# Supply_Magneto.net
KiCad netlist of a schematic drawn in Altium Designer
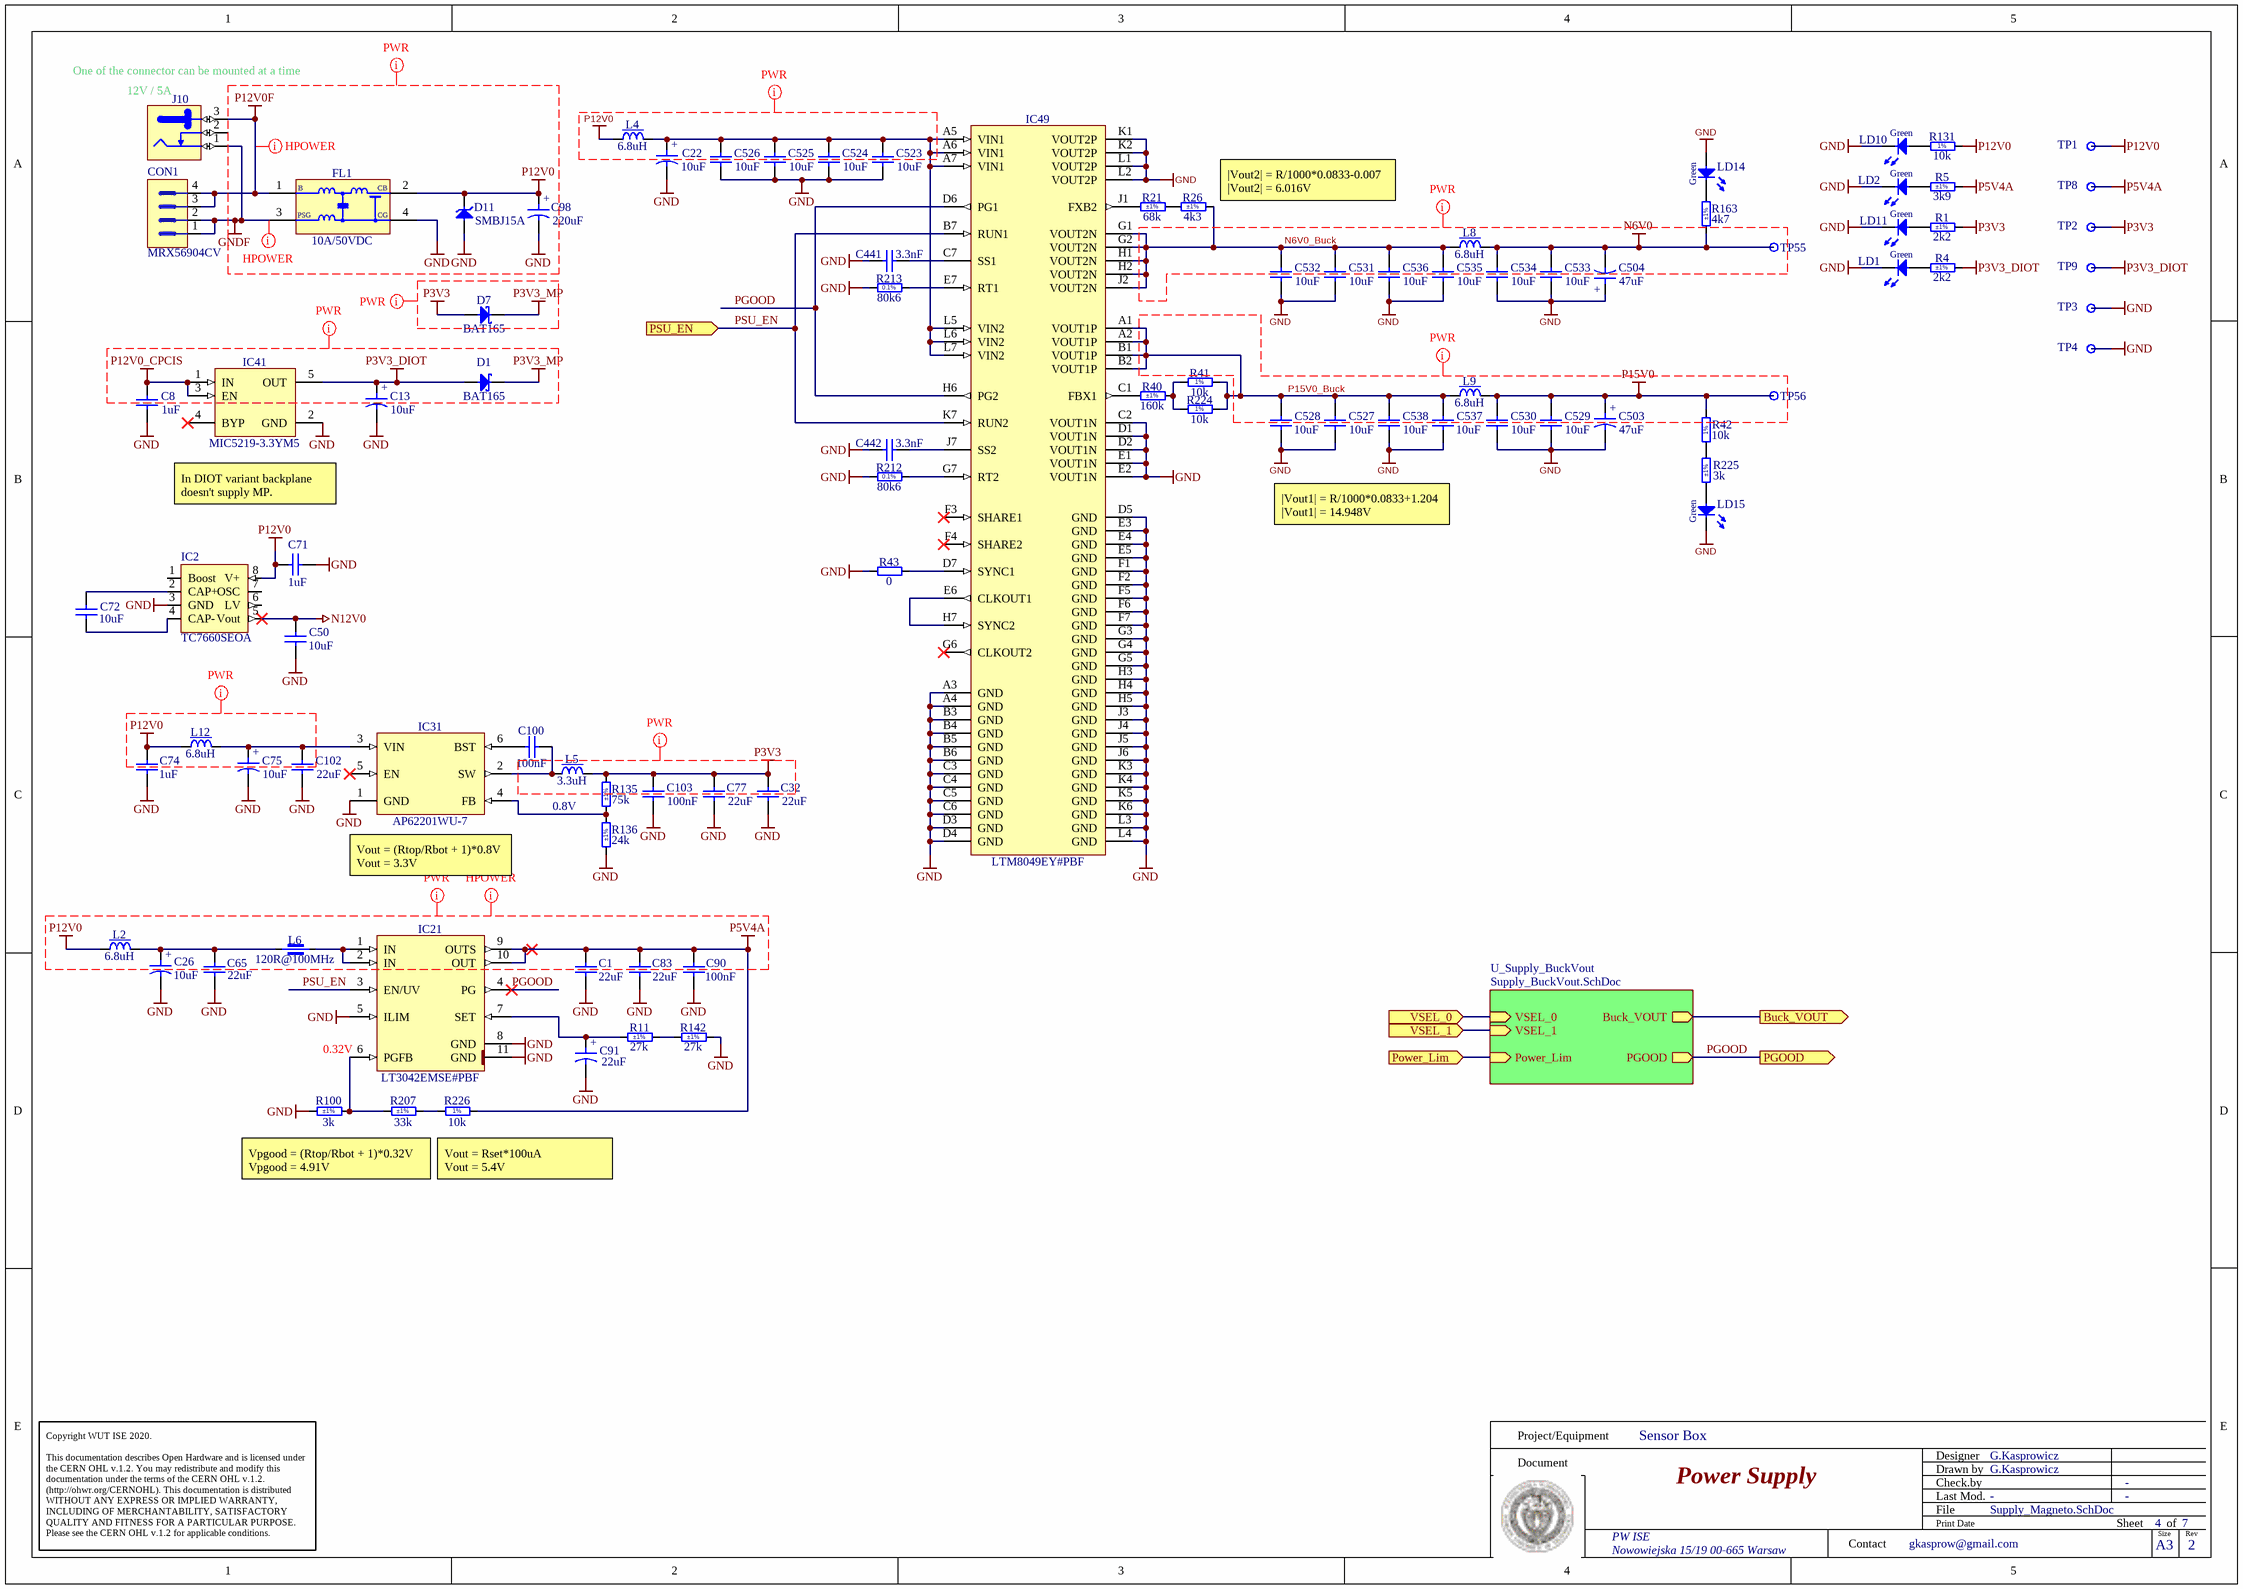
[diagram p0: Supply_Magneto.SchDoc]

(export (version "E")
  (design (tool "Eeschema 10.0.6"))
  (components
    (comp (ref "C1")
      (value "22uF")
      (footprint "CAPC2012X135N")
      (description "Non-polarised capacitor")
      (fields (field (name "PART NUMBER") "CC0805_22UF_16V_10%_X5R") (field (name "VOLTAGE") "16V"))
      (libsource (lib "Capacitors") (part "Capacitor - non polarized"))
    )
    (comp (ref "C8")
      (value "1uF")
      (footprint "CAPC1608X87N")
      (description "Non-polarised capacitor")
      (fields (field (name "PART NUMBER") "CC0603_1UF_25V_10%_X7R") (field (name "VOLTAGE") "25V"))
      (libsource (lib "Capacitors") (part "Capacitor - non polarized"))
    )
    (comp (ref "C13")
      (value "10uF")
      (footprint "CAPMP3216X180N")
      (description "Polarised capacitor")
      (fields (field (name "PART NUMBER") "CTE3216-18_10UF_16V_20%_AVX_TCJ") (field (name "VOLTAGE") "16V"))
      (libsource (lib "Capacitors") (part "Capacitor - polarized"))
    )
    (comp (ref "C22")
      (value "10uF")
      (footprint "CAPMP3216X180N")
      (description "Polarised capacitor")
      (fields (field (name "PART NUMBER") "CTE3216-18_10UF_16V_20%_AVX_TCJ") (field (name "VOLTAGE") "16V"))
      (libsource (lib "Capacitors") (part "Capacitor - polarized"))
    )
    (comp (ref "C26")
      (value "10uF")
      (footprint "CAPMP3216X180N")
      (description "Polarised capacitor")
      (fields (field (name "PART NUMBER") "CTE3216-18_10UF_16V_20%_AVX_TCJ") (field (name "VOLTAGE") "16V"))
      (libsource (lib "Capacitors") (part "Capacitor - polarized"))
    )
    (comp (ref "C32")
      (value "22uF")
      (footprint "CAPC2012X135N")
      (description "Non-polarised capacitor")
      (fields (field (name "PART NUMBER") "CC0805_22UF_16V_10%_X5R") (field (name "VOLTAGE") "16V"))
      (libsource (lib "Capacitors") (part "Capacitor - non polarized"))
    )
    (comp (ref "C50")
      (value "10uF")
      (footprint "CAPC1608X80N")
      (description "Non-polarised capacitor")
      (fields (field (name "PART NUMBER") "CC0603_10UF_16V_20%_X5R") (field (name "VOLTAGE") "16V"))
      (libsource (lib "Capacitors") (part "Capacitor - non polarized"))
    )
    (comp (ref "C65")
      (value "22uF")
      (footprint "CAPC2012X135N")
      (description "Non-polarised capacitor")
      (fields (field (name "PART NUMBER") "CC0805_22UF_16V_10%_X5R") (field (name "VOLTAGE") "16V"))
      (libsource (lib "Capacitors") (part "Capacitor - non polarized"))
    )
    (comp (ref "C71")
      (value "1uF")
      (footprint "CAPC1608X87N")
      (description "Non-polarised capacitor")
      (fields (field (name "PART NUMBER") "CC0603_1UF_25V_10%_X7R") (field (name "VOLTAGE") "25V"))
      (libsource (lib "Capacitors") (part "Capacitor - non polarized"))
    )
    (comp (ref "C72")
      (value "10uF")
      (footprint "CAPC1608X80N")
      (description "Non-polarised capacitor")
      (fields (field (name "PART NUMBER") "CC0603_10UF_16V_20%_X5R") (field (name "VOLTAGE") "16V"))
      (libsource (lib "Capacitors") (part "Capacitor - non polarized"))
    )
    (comp (ref "C74")
      (value "1uF")
      (footprint "CAPC1608X87N")
      (description "Non-polarised capacitor")
      (fields (field (name "PART NUMBER") "CC0603_1UF_25V_10%_X7R") (field (name "VOLTAGE") "25V"))
      (libsource (lib "Capacitors") (part "Capacitor - non polarized"))
    )
    (comp (ref "C75")
      (value "10uF")
      (footprint "CAPMP3216X180N")
      (description "Polarised capacitor")
      (fields (field (name "PART NUMBER") "CTE3216-18_10UF_16V_20%_AVX_TCJ") (field (name "VOLTAGE") "16V"))
      (libsource (lib "Capacitors") (part "Capacitor - polarized"))
    )
    (comp (ref "C77")
      (value "22uF")
      (footprint "CAPC2012X135N")
      (description "Non-polarised capacitor")
      (fields (field (name "PART NUMBER") "CC0805_22UF_16V_10%_X5R") (field (name "VOLTAGE") "16V"))
      (libsource (lib "Capacitors") (part "Capacitor - non polarized"))
    )
    (comp (ref "C83")
      (value "22uF")
      (footprint "CAPC2012X135N")
      (description "Non-polarised capacitor")
      (fields (field (name "PART NUMBER") "CC0805_22UF_16V_10%_X5R") (field (name "VOLTAGE") "16V"))
      (libsource (lib "Capacitors") (part "Capacitor - non polarized"))
    )
    (comp (ref "C90")
      (value "100nF")
      (footprint "CAPC1005X55N")
      (description "Non-polarised capacitor")
      (fields (field (name "PART NUMBER") "CC0402_100NF_16V_10%_X5R") (field (name "VOLTAGE") "16V"))
      (libsource (lib "Capacitors") (part "Capacitor - non polarized"))
    )
    (comp (ref "C91")
      (value "22uF")
      (footprint "CAPMP3528X210N")
      (description "Polarised capacitor")
      (fields (field (name "PART NUMBER") "CTE3528-21_22UF_10V_10%_LESR0700") (field (name "VOLTAGE") "10V"))
      (libsource (lib "Capacitors") (part "Capacitor - polarized"))
    )
    (comp (ref "C98")
      (value "220uF")
      (footprint "CAPAE830X620N")
      (description "Polarised capacitor")
      (fields (field (name "PART NUMBER") "CAE830-620_220UF_16V_20%") (field (name "VOLTAGE") "16V"))
      (libsource (lib "Capacitors") (part "Capacitor - polarized"))
    )
    (comp (ref "C100")
      (value "100nF")
      (footprint "CAPC1005X55N")
      (description "Non-polarised capacitor")
      (fields (field (name "PART NUMBER") "CC0402_100NF_16V_10%_X5R") (field (name "VOLTAGE") "16V"))
      (libsource (lib "Capacitors") (part "Capacitor - non polarized"))
    )
    (comp (ref "C102")
      (value "22uF")
      (footprint "CAPC2012X135N")
      (description "Non-polarised capacitor")
      (fields (field (name "PART NUMBER") "CC0805_22UF_16V_10%_X5R") (field (name "VOLTAGE") "16V"))
      (libsource (lib "Capacitors") (part "Capacitor - non polarized"))
    )
    (comp (ref "C103")
      (value "100nF")
      (footprint "CAPC1005X55N")
      (description "Non-polarised capacitor")
      (fields (field (name "PART NUMBER") "CC0402_100NF_16V_10%_X5R") (field (name "VOLTAGE") "16V"))
      (libsource (lib "Capacitors") (part "Capacitor - non polarized"))
    )
    (comp (ref "C441")
      (value "3.3nF")
      (footprint "CAPC1005X55N")
      (description "Non-polarised capacitor")
      (fields
        (field (name "MANUFACTURER PART NUMBER") "CC0402_3.3NF_50V_10%_X7R")
        (field (name "MANUFACTURER") "GENERIC")
      )
      (libsource (lib "Capacitors") (part "Capacitor - non polarized"))
    )
    (comp (ref "C442")
      (value "3.3nF")
      (footprint "CAPC1005X55N")
      (description "Non-polarised capacitor")
      (fields
        (field (name "MANUFACTURER PART NUMBER") "CC0402_3.3NF_50V_10%_X7R")
        (field (name "MANUFACTURER") "GENERIC")
      )
      (libsource (lib "Capacitors") (part "Capacitor - non polarized"))
    )
    (comp (ref "C503")
      (value "47uF")
      (footprint "CAPMP6032X280N")
      (description "Polarised capacitor")
      (fields
        (field (name "MANUFACTURER PART NUMBER") "CTE6032-28_47UF_16V_10%_LESR0350")
        (field (name "MANUFACTURER") "GENERIC")
      )
      (libsource (lib "Capacitors") (part "Capacitor - polarized"))
    )
    (comp (ref "C504")
      (value "47uF")
      (footprint "CAPMP6032X280N")
      (description "Polarised capacitor")
      (fields
        (field (name "MANUFACTURER PART NUMBER") "CTE6032-28_47UF_16V_10%_LESR0350")
        (field (name "MANUFACTURER") "GENERIC")
      )
      (libsource (lib "Capacitors") (part "Capacitor - polarized"))
    )
    (comp (ref "C523")
      (value "10uF")
      (footprint "CAPC2012X95N")
      (description "Non-polarised capacitor")
      (fields
        (field (name "MANUFACTURER PART NUMBER") "CC0805_10UF_25V_10%_X5R")
        (field (name "MANUFACTURER") "GENERIC")
      )
      (libsource (lib "Capacitors") (part "Capacitor - non polarized"))
    )
    (comp (ref "C524")
      (value "10uF")
      (footprint "CAPC2012X95N")
      (description "Non-polarised capacitor")
      (fields
        (field (name "MANUFACTURER PART NUMBER") "CC0805_10UF_25V_10%_X5R")
        (field (name "MANUFACTURER") "GENERIC")
      )
      (libsource (lib "Capacitors") (part "Capacitor - non polarized"))
    )
    (comp (ref "C525")
      (value "10uF")
      (footprint "CAPC2012X95N")
      (description "Non-polarised capacitor")
      (fields
        (field (name "MANUFACTURER PART NUMBER") "CC0805_10UF_25V_10%_X5R")
        (field (name "MANUFACTURER") "GENERIC")
      )
      (libsource (lib "Capacitors") (part "Capacitor - non polarized"))
    )
    (comp (ref "C526")
      (value "10uF")
      (footprint "CAPC2012X95N")
      (description "Non-polarised capacitor")
      (fields
        (field (name "MANUFACTURER PART NUMBER") "CC0805_10UF_25V_10%_X5R")
        (field (name "MANUFACTURER") "GENERIC")
      )
      (libsource (lib "Capacitors") (part "Capacitor - non polarized"))
    )
    (comp (ref "C527")
      (value "10uF")
      (footprint "CAPC2012X95N")
      (description "Non-polarised capacitor")
      (fields
        (field (name "MANUFACTURER PART NUMBER") "CC0805_10UF_25V_10%_X5R")
        (field (name "MANUFACTURER") "GENERIC")
      )
      (libsource (lib "Capacitors") (part "Capacitor - non polarized"))
    )
    (comp (ref "C528")
      (value "10uF")
      (footprint "CAPC2012X95N")
      (description "Non-polarised capacitor")
      (fields
        (field (name "MANUFACTURER PART NUMBER") "CC0805_10UF_25V_10%_X5R")
        (field (name "MANUFACTURER") "GENERIC")
      )
      (libsource (lib "Capacitors") (part "Capacitor - non polarized"))
    )
    (comp (ref "C529")
      (value "10uF")
      (footprint "CAPC2012X95N")
      (description "Non-polarised capacitor")
      (fields
        (field (name "MANUFACTURER PART NUMBER") "CC0805_10UF_25V_10%_X5R")
        (field (name "MANUFACTURER") "GENERIC")
      )
      (libsource (lib "Capacitors") (part "Capacitor - non polarized"))
    )
    (comp (ref "C530")
      (value "10uF")
      (footprint "CAPC2012X95N")
      (description "Non-polarised capacitor")
      (fields
        (field (name "MANUFACTURER PART NUMBER") "CC0805_10UF_25V_10%_X5R")
        (field (name "MANUFACTURER") "GENERIC")
      )
      (libsource (lib "Capacitors") (part "Capacitor - non polarized"))
    )
    (comp (ref "C531")
      (value "10uF")
      (footprint "CAPC2012X95N")
      (description "Non-polarised capacitor")
      (fields
        (field (name "MANUFACTURER PART NUMBER") "CC0805_10UF_25V_10%_X5R")
        (field (name "MANUFACTURER") "GENERIC")
      )
      (libsource (lib "Capacitors") (part "Capacitor - non polarized"))
    )
    (comp (ref "C532")
      (value "10uF")
      (footprint "CAPC2012X95N")
      (description "Non-polarised capacitor")
      (fields
        (field (name "MANUFACTURER PART NUMBER") "CC0805_10UF_25V_10%_X5R")
        (field (name "MANUFACTURER") "GENERIC")
      )
      (libsource (lib "Capacitors") (part "Capacitor - non polarized"))
    )
    (comp (ref "C533")
      (value "10uF")
      (footprint "CAPC2012X95N")
      (description "Non-polarised capacitor")
      (fields
        (field (name "MANUFACTURER PART NUMBER") "CC0805_10UF_25V_10%_X5R")
        (field (name "MANUFACTURER") "GENERIC")
      )
      (libsource (lib "Capacitors") (part "Capacitor - non polarized"))
    )
    (comp (ref "C534")
      (value "10uF")
      (footprint "CAPC2012X95N")
      (description "Non-polarised capacitor")
      (fields
        (field (name "MANUFACTURER PART NUMBER") "CC0805_10UF_25V_10%_X5R")
        (field (name "MANUFACTURER") "GENERIC")
      )
      (libsource (lib "Capacitors") (part "Capacitor - non polarized"))
    )
    (comp (ref "C535")
      (value "10uF")
      (footprint "CAPC2012X95N")
      (description "Non-polarised capacitor")
      (fields
        (field (name "MANUFACTURER PART NUMBER") "CC0805_10UF_25V_10%_X5R")
        (field (name "MANUFACTURER") "GENERIC")
      )
      (libsource (lib "Capacitors") (part "Capacitor - non polarized"))
    )
    (comp (ref "C536")
      (value "10uF")
      (footprint "CAPC2012X95N")
      (description "Non-polarised capacitor")
      (fields
        (field (name "MANUFACTURER PART NUMBER") "CC0805_10UF_25V_10%_X5R")
        (field (name "MANUFACTURER") "GENERIC")
      )
      (libsource (lib "Capacitors") (part "Capacitor - non polarized"))
    )
    (comp (ref "C537")
      (value "10uF")
      (footprint "CAPC2012X95N")
      (description "Non-polarised capacitor")
      (fields
        (field (name "MANUFACTURER PART NUMBER") "CC0805_10UF_25V_10%_X5R")
        (field (name "MANUFACTURER") "GENERIC")
      )
      (libsource (lib "Capacitors") (part "Capacitor - non polarized"))
    )
    (comp (ref "C538")
      (value "10uF")
      (footprint "CAPC2012X95N")
      (description "Non-polarised capacitor")
      (fields
        (field (name "MANUFACTURER PART NUMBER") "CC0805_10UF_25V_10%_X5R")
        (field (name "MANUFACTURER") "GENERIC")
      )
      (libsource (lib "Capacitors") (part "Capacitor - non polarized"))
    )
    (comp (ref "CON1")
      (value "MRX56904CV")
      (footprint "MRX56904CV")
      (description "4.2mm cripm terminal header")
      (fields (field (name "MANUFACTURER1 PART NUMBER") "64900429522"))
      (libsource (lib "LIBRARY_SCH") (part "CON_CRIMP_4.2mm_RA_4"))
    )
    (comp (ref "D1")
      (value "BAT165")
      (footprint "SOD2512X110N")
      (description "Schottky Diode")
      (fields (field (name "MANUFACTURER") "INFINEON") (field (name "VOLTAGE") "40V"))
      (libsource (lib "ICs And Semiconductors") (part "Diode Schottky"))
    )
    (comp (ref "D7")
      (value "BAT165")
      (footprint "SOD2512X110N")
      (description "Schottky Diode")
      (fields (field (name "VOLTAGE") "40V") (field (name "POWER") "750mA"))
      (libsource (lib "ICs And Semiconductors") (part "Diode Schottky"))
    )
    (comp (ref "D11")
      (value "SMBJ15A")
      (footprint "DIOM5336X265N")
      (description "Zener Diode")
      (fields (field (name "VOLTAGE") "15V") (field (name "POWER") "600W"))
      (libsource (lib "ICs And Semiconductors") (part "Diode Zener"))
    )
    (comp (ref "FL1")
      (value "10A/50VDC")
      (footprint "FIL_MURATA_BNX02")
      (description "Block Type EMIFIL (LC Combined)")
      (fields
        (field (name "PART NUMBER") "FIL_MURATA_BNX022-01L")
        (field (name "MANUFACTURER1 PART NUMBER") "BNX022-01L")
      )
      (libsource (lib "Inductors & Transformers") (part "FIL_MURATA_BNX02"))
    )
    (comp (ref "IC2")
      (value "TC7660SEOA")
      (footprint "SO-8")
      (description "20mA PUMP DC-TO-DC VOLTAGE CONVERTER")
      (libsource (lib "LIBRARY_SCH") (part "PM_TC7660"))
    )
    (comp (ref "IC21")
      (value "LT3042EMSE#PBF")
      (footprint "SOP50P490X110-11N-R168X198")
      (description "20V, 200mA, Ultralow Noise, Ultrahigh PSRR RF Linear Regulator")
      (libsource (lib "ICs And Semiconductors") (part "LT3042"))
    )
    (comp (ref "IC31")
      (value "AP62201WU-7")
      (footprint "SOT95P280X100-6N")
      (description "4.2V TO 18V INPUT, 2A LOW IQ SYNCHRONOUS BUCK CONVERTER")
      (libsource (lib "ICs And Semiconductors") (part "AP62201WU"))
    )
    (comp (ref "IC41")
      (value "MIC5219-3.3YM5")
      (footprint "SOT95P280X145-5N")
      (description "500mA Peak Output LDO Regulator")
      (fields (field (name "MANUFACTURER1 PART NUMBER") "MIC5219-3.3YM5-TR"))
      (libsource (lib "ICs And Semiconductors") (part "MIC5219-X.XYM5"))
    )
    (comp (ref "IC49")
      (value "LTM8049EY#PBF")
      (footprint "BGA77C127P7X11_900X1500X262")
      (description "Dual SEPIC or Inverting uModule DC/DC Converter")
      (libsource (lib "ICs And Semiconductors") (part "LTM8049"))
    )
    (comp (ref "J10")
      (value "Jack")
      (footprint "SWITCHCRAFT_L712RA")
      (description "24V /3. 5A, 2.1mm Diameter Pin, SMD DC Power Supply Connector With  Break Contact")
      (fields (field (name "PART NUMBER") "SWITCHCRAFT_L712RA") (field (name "MANUFACTURER") "SWITCHCRAFT"))
      (libsource (lib "LIBRARY_SCH") (part "CON_DC_5A_THT_RA"))
    )
    (comp (ref "L2")
      (value "6.8uH")
      (footprint "IND_COILCRAFT_XAL4030")
      (description "Inductor With Core")
      (fields (field (name "PART NUMBER") "IND_6.8UH_20%_COILCRAFT_XAL4030") (field (name "POWER") "3A"))
      (libsource (lib "Inductors & Transformers") (part "Inductor With Magnetic core"))
    )
    (comp (ref "L4")
      (value "6.8uH")
      (footprint "IND_COILCRAFT_XAL4030")
      (description "Inductor With Core")
      (fields (field (name "PART NUMBER") "IND_6.8UH_20%_COILCRAFT_XAL4030") (field (name "POWER") "3A"))
      (libsource (lib "Inductors & Transformers") (part "Inductor With Magnetic core"))
    )
    (comp (ref "L5")
      (value "3.3uH")
      (footprint "IND_WURTH_WE-TPC_4828")
      (description "Inductor With Core")
      (fields
        (field (name "PART NUMBER") "IND_3.3UH_30%_WURTH_WE-TPC_744043003")
        (field (name "POWER") "2.15A")
      )
      (libsource (lib "Inductors & Transformers") (part "Inductor With Magnetic core"))
    )
    (comp (ref "L6")
      (value "120R@100MHz")
      (footprint "INDC1608X65N")
      (fields
        (field (name "PART NUMBER") "IND0603_MURATA_BLM18SG121TN1D")
        (field (name "POWER") "3A")
        (field (name "TOLERANCE") "±25%")
      )
      (libsource (lib "Inductors & Transformers") (part "Ferrite Bead"))
    )
    (comp (ref "L8")
      (value "6.8uH")
      (footprint "IND_COILCRAFT_XAL4030")
      (description "Inductor With Core")
      (fields (field (name "PART NUMBER") "IND_6.8UH_20%_COILCRAFT_XAL4030") (field (name "POWER") "3A"))
      (libsource (lib "Inductors & Transformers") (part "Inductor With Magnetic core"))
    )
    (comp (ref "L9")
      (value "6.8uH")
      (footprint "IND_COILCRAFT_XAL4030")
      (description "Inductor With Core")
      (fields (field (name "PART NUMBER") "IND_6.8UH_20%_COILCRAFT_XAL4030") (field (name "POWER") "3A"))
      (libsource (lib "Inductors & Transformers") (part "Inductor With Magnetic core"))
    )
    (comp (ref "L12")
      (value "6.8uH")
      (footprint "IND_COILCRAFT_XAL4030")
      (description "Inductor With Core")
      (fields (field (name "PART NUMBER") "IND_6.8UH_20%_COILCRAFT_XAL4030") (field (name "POWER") "3A"))
      (libsource (lib "Inductors & Transformers") (part "Inductor With Magnetic core"))
    )
    (comp (ref "LD1")
      (value "Green")
      (footprint "LED_KINGBRIGHT_KPH-1608CGCK")
      (description "LED Green 1C 2A")
      (fields
        (field (name "PART NUMBER") "LED_KINGBRIGHT_KPH-1608CGCK")
        (field (name "MANUFACTURER1 PART NUMBER") "KPH-1608CGCK")
      )
      (libsource (lib "ICs And Semiconductors") (part "LED Green 1C 2A"))
    )
    (comp (ref "LD2")
      (value "Green")
      (footprint "LED_KINGBRIGHT_KPH-1608CGCK")
      (description "LED Green 1C 2A")
      (fields
        (field (name "PART NUMBER") "LED_KINGBRIGHT_KPH-1608CGCK")
        (field (name "MANUFACTURER1 PART NUMBER") "KPH-1608CGCK")
      )
      (libsource (lib "ICs And Semiconductors") (part "LED Green 1C 2A"))
    )
    (comp (ref "LD10")
      (value "Green")
      (footprint "LED_KINGBRIGHT_KPH-1608CGCK")
      (description "LED Green 1C 2A")
      (fields
        (field (name "PART NUMBER") "LED_KINGBRIGHT_KPH-1608CGCK")
        (field (name "MANUFACTURER1 PART NUMBER") "KPH-1608CGCK")
      )
      (libsource (lib "ICs And Semiconductors") (part "LED Green 1C 2A"))
    )
    (comp (ref "LD11")
      (value "Green")
      (footprint "LED_KINGBRIGHT_KPH-1608CGCK")
      (description "LED Green 1C 2A")
      (fields
        (field (name "PART NUMBER") "LED_KINGBRIGHT_KPH-1608CGCK")
        (field (name "MANUFACTURER1 PART NUMBER") "KPH-1608CGCK")
      )
      (libsource (lib "ICs And Semiconductors") (part "LED Green 1C 2A"))
    )
    (comp (ref "LD14")
      (value "Green")
      (footprint "LED_KINGBRIGHT_KPH-1608CGCK")
      (description "LED Green 1C 2A")
      (fields
        (field (name "MANUFACTURER1 PART NUMBER") "KPH-1608CGCK")
        (field (name "PART NUMBER") "LED_KINGBRIGHT_KPH-1608CGCK")
      )
      (libsource (lib "ICs And Semiconductors") (part "LED Green 1C 2A"))
    )
    (comp (ref "LD15")
      (value "Green")
      (footprint "LED_KINGBRIGHT_KPH-1608CGCK")
      (description "LED Green 1C 2A")
      (fields
        (field (name "MANUFACTURER1 PART NUMBER") "KPH-1608CGCK")
        (field (name "PART NUMBER") "LED_KINGBRIGHT_KPH-1608CGCK")
      )
      (libsource (lib "ICs And Semiconductors") (part "LED Green 1C 2A"))
    )
    (comp (ref "R1")
      (value "2k2")
      (footprint "RESC1608X55N")
      (description "Resistor - 1%")
      (fields
        (field (name "TOLERANCE") "±1%")
        (field (name "PART NUMBER") "R0603_2K2_1%_0.1W_100PPM")
        (field (name "POWER") "0.1W")
      )
      (libsource (lib "") (part "Resistor - 1%_1"))
    )
    (comp (ref "R4")
      (value "2k2")
      (footprint "RESC1608X55N")
      (description "Resistor - 1%")
      (fields
        (field (name "TOLERANCE") "±1%")
        (field (name "PART NUMBER") "R0603_2K2_1%_0.1W_100PPM")
        (field (name "POWER") "0.1W")
      )
      (libsource (lib "") (part "Resistor - 1%_1"))
    )
    (comp (ref "R5")
      (value "3k9")
      (footprint "RESC1005X40N")
      (description "Resistor - 1%")
      (fields
        (field (name "TOLERANCE") "±1%")
        (field (name "PART NUMBER") "R0402_3K9_1%_0.0625W_100PPM")
        (field (name "POWER") "0.0625W")
      )
      (libsource (lib "Resistors") (part "Resistor - 1%"))
    )
    (comp (ref "R11")
      (value "27k")
      (footprint "RESC1608X55N")
      (description "Resistor - 1%")
      (fields
        (field (name "TOLERANCE") "±1%")
        (field (name "PART NUMBER") "R0603_27K_1%_0.1W_100PPM")
        (field (name "POWER") "0.1W")
      )
      (libsource (lib "") (part "Resistor - 1%_1"))
    )
    (comp (ref "R21")
      (value "68k")
      (footprint "RESC1608X55N")
      (description "Resistor - 1%")
      (fields
        (field (name "TOLERANCE") "±1%")
        (field (name "PART NUMBER") "R0603_68K_1%_0.1W_100PPM")
        (field (name "POWER") "0.1W")
      )
      (libsource (lib "") (part "Resistor - 1%_1"))
    )
    (comp (ref "R26")
      (value "4k3")
      (footprint "RESC1608X55N")
      (description "Resistor - 1%")
      (fields
        (field (name "TOLERANCE") "±1%")
        (field (name "PART NUMBER") "R0603_4K3_1%_0.1W_100PPM")
        (field (name "POWER") "0.1W")
      )
      (libsource (lib "") (part "Resistor - 1%_1"))
    )
    (comp (ref "R40")
      (value "160k")
      (footprint "RESC1608X55N")
      (description "Resistor - 1%")
      (fields
        (field (name "TOLERANCE") "±1%")
        (field (name "PART NUMBER") "R0603_160K_1%_0.1W_100PPM")
        (field (name "POWER") "0.1W")
      )
      (libsource (lib "") (part "Resistor - 1%_1"))
    )
    (comp (ref "R41")
      (value "10k")
      (footprint "RESC1005X40N")
      (description "Resistor - 1%")
      (fields (field (name "PART NUMBER") "R0402_10K_1%_0.0625W_100PPM") (field (name "POWER") "0.0625W"))
      (libsource (lib "Resistors") (part "Resistor - 1%"))
    )
    (comp (ref "R42")
      (value "10k")
      (footprint "RESC1005X40N")
      (description "Resistor - 1%")
      (fields (field (name "PART NUMBER") "R0402_10K_1%_0.0625W_100PPM") (field (name "POWER") "0.0625W"))
      (libsource (lib "Resistors") (part "Resistor - 1%"))
    )
    (comp (ref "R43")
      (value "0")
      (footprint "RESC1005X40N")
      (description "Resistor")
      (fields
        (field (name "MANUFACTURER PART NUMBER") "R0402_0R_JUMPER")
        (field (name "MANUFACTURER") "GENERIC")
      )
      (libsource (lib "Resistors") (part "Resistor"))
    )
    (comp (ref "R100")
      (value "3k")
      (footprint "RESC1005X40N")
      (description "Resistor - 1%")
      (fields
        (field (name "TOLERANCE") "±1%")
        (field (name "PART NUMBER") "R0402_3K_1%_0.0625W_100PPM")
        (field (name "POWER") "0.0625W")
      )
      (libsource (lib "Resistors") (part "Resistor - 1%"))
    )
    (comp (ref "R131")
      (value "10k")
      (footprint "RESC1005X40N")
      (description "Resistor - 1%")
      (fields (field (name "PART NUMBER") "R0402_10K_1%_0.0625W_100PPM") (field (name "POWER") "0.0625W"))
      (libsource (lib "Resistors") (part "Resistor - 1%"))
    )
    (comp (ref "R135")
      (value "75k")
      (footprint "RESC1608X55N")
      (description "Resistor - 1%")
      (fields
        (field (name "TOLERANCE") "±1%")
        (field (name "PART NUMBER") "R0603_75K_1%_0.1W_100PPM")
        (field (name "POWER") "0.1W")
      )
      (libsource (lib "") (part "Resistor - 1%_1"))
    )
    (comp (ref "R136")
      (value "24k")
      (footprint "RESC1608X55N")
      (description "Resistor - 1%")
      (fields
        (field (name "TOLERANCE") "±1%")
        (field (name "PART NUMBER") "R0603_24K_1%_0.1W_100PPM")
        (field (name "POWER") "0.1W")
      )
      (libsource (lib "") (part "Resistor - 1%_1"))
    )
    (comp (ref "R142")
      (value "27k")
      (footprint "RESC1608X55N")
      (description "Resistor - 1%")
      (fields
        (field (name "TOLERANCE") "±1%")
        (field (name "PART NUMBER") "R0603_27K_1%_0.1W_100PPM")
        (field (name "POWER") "0.1W")
      )
      (libsource (lib "") (part "Resistor - 1%_1"))
    )
    (comp (ref "R163")
      (value "4k7")
      (footprint "RESC1608X55N")
      (description "Resistor - 1%")
      (fields
        (field (name "TOLERANCE") "±1%")
        (field (name "PART NUMBER") "R0603_4K7_1%_0.1W_100PPM")
        (field (name "POWER") "0.1W")
      )
      (libsource (lib "") (part "Resistor - 1%_1"))
    )
    (comp (ref "R207")
      (value "33k")
      (footprint "RESC1608X55N")
      (description "Resistor - 1%")
      (fields
        (field (name "TOLERANCE") "±1%")
        (field (name "PART NUMBER") "R0603_33K_1%_0.1W_100PPM")
        (field (name "POWER") "0.1W")
      )
      (libsource (lib "") (part "Resistor - 1%_1"))
    )
    (comp (ref "R212")
      (value "80k6")
      (footprint "RESC1608X55N")
      (description "Resistor - 0.1%")
      (fields
        (field (name "MANUFACTURER PART NUMBER") "R0603_80K6_0.1%_0.063W_10PPM")
        (field (name "MANUFACTURER") "GENERIC")
      )
      (libsource (lib "Resistors") (part "Resistor - 0.1%"))
    )
    (comp (ref "R213")
      (value "80k6")
      (footprint "RESC1608X55N")
      (description "Resistor - 0.1%")
      (fields
        (field (name "MANUFACTURER PART NUMBER") "R0603_80K6_0.1%_0.063W_10PPM")
        (field (name "MANUFACTURER") "GENERIC")
      )
      (libsource (lib "Resistors") (part "Resistor - 0.1%"))
    )
    (comp (ref "R224")
      (value "10k")
      (footprint "RESC1005X40N")
      (description "Resistor - 1%")
      (fields (field (name "PART NUMBER") "R0402_10K_1%_0.0625W_100PPM") (field (name "POWER") "0.0625W"))
      (libsource (lib "Resistors") (part "Resistor - 1%"))
    )
    (comp (ref "R225")
      (value "3k")
      (footprint "RESC1005X40N")
      (description "Resistor - 1%")
      (fields
        (field (name "TOLERANCE") "±1%")
        (field (name "PART NUMBER") "R0402_3K_1%_0.0625W_100PPM")
        (field (name "POWER") "0.0625W")
      )
      (libsource (lib "Resistors") (part "Resistor - 1%"))
    )
    (comp (ref "R226")
      (value "10k")
      (footprint "RESC1005X40N")
      (description "Resistor - 1%")
      (fields (field (name "PART NUMBER") "R0402_10K_1%_0.0625W_100PPM") (field (name "POWER") "0.0625W"))
      (libsource (lib "Resistors") (part "Resistor - 1%"))
    )
    (comp (ref "TP1")
      (value "Test Point")
      (footprint "TPS127")
      (fields (field (name "PART NUMBER") "SMD_PAD_1.27X1.27MM"))
      (libsource (lib "Eletro-mechanical") (part "Test Point"))
    )
    (comp (ref "TP2")
      (value "Test Point")
      (footprint "TPS127")
      (fields (field (name "PART NUMBER") "SMD_PAD_1.27X1.27MM"))
      (libsource (lib "Eletro-mechanical") (part "Test Point"))
    )
    (comp (ref "TP3")
      (value "Test Point")
      (footprint "TPS127")
      (fields (field (name "PART NUMBER") "SMD_PAD_1.27X1.27MM"))
      (libsource (lib "Eletro-mechanical") (part "Test Point"))
    )
    (comp (ref "TP4")
      (value "Test Point")
      (footprint "TPS127")
      (fields (field (name "PART NUMBER") "SMD_PAD_1.27X1.27MM"))
      (libsource (lib "Eletro-mechanical") (part "Test Point"))
    )
    (comp (ref "TP8")
      (value "Test Point")
      (footprint "TPS127")
      (fields (field (name "PART NUMBER") "SMD_PAD_1.27X1.27MM"))
      (libsource (lib "Eletro-mechanical") (part "Test Point"))
    )
    (comp (ref "TP9")
      (value "Test Point")
      (footprint "TPS127")
      (fields (field (name "PART NUMBER") "SMD_PAD_1.27X1.27MM"))
      (libsource (lib "Eletro-mechanical") (part "Test Point"))
    )
    (comp (ref "TP55")
      (value "Test Point")
      (footprint "TPS127")
      (fields (field (name "PART NUMBER") "SMD_PAD_1.27X1.27MM"))
      (libsource (lib "Eletro-mechanical") (part "Test Point"))
    )
    (comp (ref "TP56")
      (value "Test Point")
      (footprint "TPS127")
      (fields (field (name "PART NUMBER") "SMD_PAD_1.27X1.27MM"))
      (libsource (lib "Eletro-mechanical") (part "Test Point"))
    )
  )
  (nets
    (net (code "2") (name "/N6V0_Buck") (class "Default")
      (node (ref "C531") (pin "2") (pinfunction "2_2") (pintype "passive"))
      (node (ref "C532") (pin "2") (pinfunction "2_2") (pintype "passive"))
      (node (ref "C535") (pin "2") (pinfunction "2_2") (pintype "passive"))
      (node (ref "C536") (pin "2") (pinfunction "2_2") (pintype "passive"))
      (node (ref "IC49") (pin "G1") (pinfunction "VOUT2N_G1") (pintype "power_in"))
      (node (ref "IC49") (pin "G2") (pinfunction "VOUT2N_G2") (pintype "power_in"))
      (node (ref "IC49") (pin "H1") (pinfunction "VOUT2N_H1") (pintype "power_in"))
      (node (ref "IC49") (pin "H2") (pinfunction "VOUT2N_H2") (pintype "power_in"))
      (node (ref "IC49") (pin "J2") (pinfunction "VOUT2N_J2") (pintype "power_in"))
      (node (ref "L8") (pin "1") (pinfunction "1_1") (pintype "passive"))
      (node (ref "R26") (pin "2") (pinfunction "2_2") (pintype "passive"))
    )
    (net (code "3") (name "/P15V0_Buck") (class "Default")
      (node (ref "C527") (pin "2") (pinfunction "2_2") (pintype "passive"))
      (node (ref "C528") (pin "2") (pinfunction "2_2") (pintype "passive"))
      (node (ref "C537") (pin "2") (pinfunction "2_2") (pintype "passive"))
      (node (ref "C538") (pin "2") (pinfunction "2_2") (pintype "passive"))
      (node (ref "IC49") (pin "A1") (pinfunction "VOUT1P_A1") (pintype "power_in"))
      (node (ref "IC49") (pin "A2") (pinfunction "VOUT1P_A2") (pintype "power_in"))
      (node (ref "IC49") (pin "B1") (pinfunction "VOUT1P_B1") (pintype "power_in"))
      (node (ref "IC49") (pin "B2") (pinfunction "VOUT1P_B2") (pintype "power_in"))
      (node (ref "L9") (pin "1") (pinfunction "1_1") (pintype "passive"))
      (node (ref "R224") (pin "2") (pinfunction "2_2") (pintype "passive"))
      (node (ref "R41") (pin "2") (pinfunction "2_2") (pintype "passive"))
    )
    (net (code "4") (name "/PGOOD") (class "Default")
      (node (ref "IC21") (pin "4") (pinfunction "PG_4") (pintype "output"))
      (node (ref "IC49") (pin "D6") (pinfunction "PG1_D6") (pintype "output"))
      (node (ref "IC49") (pin "H6") (pinfunction "PG2_H6") (pintype "output"))
    )
    (net (code "5") (name "/PSU_EN") (class "Default")
      (node (ref "IC21") (pin "3") (pinfunction "EN/UV_3") (pintype "input"))
      (node (ref "IC49") (pin "B7") (pinfunction "RUN1_B7") (pintype "input"))
      (node (ref "IC49") (pin "K7") (pinfunction "RUN2_K7") (pintype "input"))
    )
    (net (code "9") (name "GND") (class "Default")
      (node (ref "C1") (pin "1") (pinfunction "1_1") (pintype "passive"))
      (node (ref "C102") (pin "1") (pinfunction "1_1") (pintype "passive"))
      (node (ref "C103") (pin "1") (pinfunction "1_1") (pintype "passive"))
      (node (ref "C13") (pin "2") (pinfunction "2_2") (pintype "passive"))
      (node (ref "C22") (pin "2") (pinfunction "2_2") (pintype "passive"))
      (node (ref "C26") (pin "2") (pinfunction "2_2") (pintype "passive"))
      (node (ref "C32") (pin "1") (pinfunction "1_1") (pintype "passive"))
      (node (ref "C441") (pin "1") (pinfunction "1_1") (pintype "passive"))
      (node (ref "C442") (pin "1") (pinfunction "1_1") (pintype "passive"))
      (node (ref "C50") (pin "1") (pinfunction "1_1") (pintype "passive"))
      (node (ref "C503") (pin "2") (pinfunction "2_2") (pintype "passive"))
      (node (ref "C504") (pin "1") (pinfunction "1_1") (pintype "passive"))
      (node (ref "C523") (pin "1") (pinfunction "1_1") (pintype "passive"))
      (node (ref "C524") (pin "1") (pinfunction "1_1") (pintype "passive"))
      (node (ref "C525") (pin "1") (pinfunction "1_1") (pintype "passive"))
      (node (ref "C526") (pin "1") (pinfunction "1_1") (pintype "passive"))
      (node (ref "C527") (pin "1") (pinfunction "1_1") (pintype "passive"))
      (node (ref "C528") (pin "1") (pinfunction "1_1") (pintype "passive"))
      (node (ref "C529") (pin "1") (pinfunction "1_1") (pintype "passive"))
      (node (ref "C530") (pin "1") (pinfunction "1_1") (pintype "passive"))
      (node (ref "C531") (pin "1") (pinfunction "1_1") (pintype "passive"))
      (node (ref "C532") (pin "1") (pinfunction "1_1") (pintype "passive"))
      (node (ref "C533") (pin "1") (pinfunction "1_1") (pintype "passive"))
      (node (ref "C534") (pin "1") (pinfunction "1_1") (pintype "passive"))
      (node (ref "C535") (pin "1") (pinfunction "1_1") (pintype "passive"))
      (node (ref "C536") (pin "1") (pinfunction "1_1") (pintype "passive"))
      (node (ref "C537") (pin "1") (pinfunction "1_1") (pintype "passive"))
      (node (ref "C538") (pin "1") (pinfunction "1_1") (pintype "passive"))
      (node (ref "C65") (pin "1") (pinfunction "1_1") (pintype "passive"))
      (node (ref "C71") (pin "1") (pinfunction "1_1") (pintype "passive"))
      (node (ref "C74") (pin "1") (pinfunction "1_1") (pintype "passive"))
      (node (ref "C75") (pin "2") (pinfunction "2_2") (pintype "passive"))
      (node (ref "C77") (pin "1") (pinfunction "1_1") (pintype "passive"))
      (node (ref "C8") (pin "1") (pinfunction "1_1") (pintype "passive"))
      (node (ref "C83") (pin "1") (pinfunction "1_1") (pintype "passive"))
      (node (ref "C90") (pin "1") (pinfunction "1_1") (pintype "passive"))
      (node (ref "C91") (pin "2") (pinfunction "2_2") (pintype "passive"))
      (node (ref "C98") (pin "2") (pinfunction "2_2") (pintype "passive"))
      (node (ref "D11") (pin "2") (pinfunction "A_2") (pintype "passive"))
      (node (ref "FL1") (pin "4") (pinfunction "CG_4") (pintype "passive"))
      (node (ref "IC2") (pin "3") (pinfunction "GND_3") (pintype "power_in"))
      (node (ref "IC21") (pin "11") (pinfunction "GND_11") (pintype "power_in"))
      (node (ref "IC21") (pin "5") (pinfunction "ILIM_5") (pintype "input"))
      (node (ref "IC21") (pin "8") (pinfunction "GND_8") (pintype "power_in"))
      (node (ref "IC31") (pin "1") (pinfunction "GND_1") (pintype "power_in"))
      (node (ref "IC41") (pin "2") (pinfunction "GND_2") (pintype "power_in"))
      (node (ref "IC49") (pin "A3") (pinfunction "GND_A3") (pintype "power_in"))
      (node (ref "IC49") (pin "A4") (pinfunction "GND_A4") (pintype "power_in"))
      (node (ref "IC49") (pin "B3") (pinfunction "GND_B3") (pintype "power_in"))
      (node (ref "IC49") (pin "B4") (pinfunction "GND_B4") (pintype "power_in"))
      (node (ref "IC49") (pin "B5") (pinfunction "GND_B5") (pintype "power_in"))
      (node (ref "IC49") (pin "B6") (pinfunction "GND_B6") (pintype "power_in"))
      (node (ref "IC49") (pin "C2") (pinfunction "VOUT1N_C2") (pintype "power_in"))
      (node (ref "IC49") (pin "C3") (pinfunction "GND_C3") (pintype "power_in"))
      (node (ref "IC49") (pin "C4") (pinfunction "GND_C4") (pintype "power_in"))
      (node (ref "IC49") (pin "C5") (pinfunction "GND_C5") (pintype "power_in"))
      (node (ref "IC49") (pin "C6") (pinfunction "GND_C6") (pintype "power_in"))
      (node (ref "IC49") (pin "D1") (pinfunction "VOUT1N_D1") (pintype "power_in"))
      (node (ref "IC49") (pin "D2") (pinfunction "VOUT1N_D2") (pintype "power_in"))
      (node (ref "IC49") (pin "D3") (pinfunction "GND_D3") (pintype "power_in"))
      (node (ref "IC49") (pin "D4") (pinfunction "GND_D4") (pintype "power_in"))
      (node (ref "IC49") (pin "D5") (pinfunction "GND_D5") (pintype "power_in"))
      (node (ref "IC49") (pin "E1") (pinfunction "VOUT1N_E1") (pintype "power_in"))
      (node (ref "IC49") (pin "E2") (pinfunction "VOUT1N_E2") (pintype "power_in"))
      (node (ref "IC49") (pin "E3") (pinfunction "GND_E3") (pintype "power_in"))
      (node (ref "IC49") (pin "E4") (pinfunction "GND_E4") (pintype "power_in"))
      (node (ref "IC49") (pin "E5") (pinfunction "GND_E5") (pintype "power_in"))
      (node (ref "IC49") (pin "F1") (pinfunction "GND_F1") (pintype "power_in"))
      (node (ref "IC49") (pin "F2") (pinfunction "GND_F2") (pintype "power_in"))
      (node (ref "IC49") (pin "F5") (pinfunction "GND_F5") (pintype "power_in"))
      (node (ref "IC49") (pin "F6") (pinfunction "GND_F6") (pintype "power_in"))
      (node (ref "IC49") (pin "F7") (pinfunction "GND_F7") (pintype "power_in"))
      (node (ref "IC49") (pin "G3") (pinfunction "GND_G3") (pintype "power_in"))
      (node (ref "IC49") (pin "G4") (pinfunction "GND_G4") (pintype "power_in"))
      (node (ref "IC49") (pin "G5") (pinfunction "GND_G5") (pintype "power_in"))
      (node (ref "IC49") (pin "H3") (pinfunction "GND_H3") (pintype "power_in"))
      (node (ref "IC49") (pin "H4") (pinfunction "GND_H4") (pintype "power_in"))
      (node (ref "IC49") (pin "H5") (pinfunction "GND_H5") (pintype "power_in"))
      (node (ref "IC49") (pin "J3") (pinfunction "GND_J3") (pintype "power_in"))
      (node (ref "IC49") (pin "J4") (pinfunction "GND_J4") (pintype "power_in"))
      (node (ref "IC49") (pin "J5") (pinfunction "GND_J5") (pintype "power_in"))
      (node (ref "IC49") (pin "J6") (pinfunction "GND_J6") (pintype "power_in"))
      (node (ref "IC49") (pin "K1") (pinfunction "VOUT2P_K1") (pintype "power_in"))
      (node (ref "IC49") (pin "K2") (pinfunction "VOUT2P_K2") (pintype "power_in"))
      (node (ref "IC49") (pin "K3") (pinfunction "GND_K3") (pintype "power_in"))
      (node (ref "IC49") (pin "K4") (pinfunction "GND_K4") (pintype "power_in"))
      (node (ref "IC49") (pin "K5") (pinfunction "GND_K5") (pintype "power_in"))
      (node (ref "IC49") (pin "K6") (pinfunction "GND_K6") (pintype "power_in"))
      (node (ref "IC49") (pin "L1") (pinfunction "VOUT2P_L1") (pintype "power_in"))
      (node (ref "IC49") (pin "L2") (pinfunction "VOUT2P_L2") (pintype "power_in"))
      (node (ref "IC49") (pin "L3") (pinfunction "GND_L3") (pintype "power_in"))
      (node (ref "IC49") (pin "L4") (pinfunction "GND_L4") (pintype "power_in"))
      (node (ref "LD1") (pin "1") (pinfunction "C_1") (pintype "passive"))
      (node (ref "LD10") (pin "1") (pinfunction "C_1") (pintype "passive"))
      (node (ref "LD11") (pin "1") (pinfunction "C_1") (pintype "passive"))
      (node (ref "LD14") (pin "2") (pinfunction "A_2") (pintype "passive"))
      (node (ref "LD15") (pin "1") (pinfunction "C_1") (pintype "passive"))
      (node (ref "LD2") (pin "1") (pinfunction "C_1") (pintype "passive"))
      (node (ref "R100") (pin "1") (pinfunction "1_1") (pintype "passive"))
      (node (ref "R136") (pin "1") (pinfunction "1_1") (pintype "passive"))
      (node (ref "R142") (pin "2") (pinfunction "2_2") (pintype "passive"))
      (node (ref "R212") (pin "1") (pinfunction "1_1") (pintype "passive"))
      (node (ref "R213") (pin "1") (pinfunction "1_1") (pintype "passive"))
      (node (ref "R43") (pin "1") (pinfunction "1_1") (pintype "passive"))
      (node (ref "TP3") (pin "1") (pinfunction "1_1") (pintype "bidirectional"))
      (node (ref "TP4") (pin "1") (pinfunction "1_1") (pintype "bidirectional"))
    )
    (net (code "10") (name "GNDF") (class "Default")
      (node (ref "CON1") (pin "1") (pinfunction "1_1") (pintype "bidirectional"))
      (node (ref "CON1") (pin "2") (pinfunction "2_2") (pintype "bidirectional"))
      (node (ref "FL1") (pin "3") (pinfunction "PSG_3") (pintype "passive"))
      (node (ref "J10") (pin "1") (pinfunction "1_1") (pintype "bidirectional"))
    )
    (net (code "11") (name "N6V0") (class "Default")
      (node (ref "C504") (pin "2") (pinfunction "2_2") (pintype "passive"))
      (node (ref "C533") (pin "2") (pinfunction "2_2") (pintype "passive"))
      (node (ref "C534") (pin "2") (pinfunction "2_2") (pintype "passive"))
      (node (ref "L8") (pin "2") (pinfunction "2_2") (pintype "passive"))
      (node (ref "R163") (pin "1") (pinfunction "1_1") (pintype "passive"))
      (node (ref "TP55") (pin "1") (pinfunction "1_1") (pintype "bidirectional"))
    )
    (net (code "12") (name "N12V0") (class "Default")
      (node (ref "C50") (pin "2") (pinfunction "2_2") (pintype "passive"))
      (node (ref "IC2") (pin "5") (pinfunction "Vout_5") (pintype "output"))
    )
    (net (code "13") (name "Net-(C22-Pad1)") (class "Default")
      (node (ref "C22") (pin "1") (pinfunction "1_1") (pintype "passive"))
      (node (ref "C523") (pin "2") (pinfunction "2_2") (pintype "passive"))
      (node (ref "C524") (pin "2") (pinfunction "2_2") (pintype "passive"))
      (node (ref "C525") (pin "2") (pinfunction "2_2") (pintype "passive"))
      (node (ref "C526") (pin "2") (pinfunction "2_2") (pintype "passive"))
      (node (ref "IC49") (pin "A5") (pinfunction "VIN1_A5") (pintype "input"))
      (node (ref "IC49") (pin "A6") (pinfunction "VIN1_A6") (pintype "input"))
      (node (ref "IC49") (pin "A7") (pinfunction "VIN1_A7") (pintype "input"))
      (node (ref "IC49") (pin "L5") (pinfunction "VIN2_L5") (pintype "input"))
      (node (ref "IC49") (pin "L6") (pinfunction "VIN2_L6") (pintype "input"))
      (node (ref "IC49") (pin "L7") (pinfunction "VIN2_L7") (pintype "input"))
      (node (ref "L4") (pin "2") (pinfunction "2_2") (pintype "passive"))
    )
    (net (code "14") (name "Net-(C26-Pad1)") (class "Default")
      (node (ref "C26") (pin "1") (pinfunction "1_1") (pintype "passive"))
      (node (ref "C65") (pin "2") (pinfunction "2_2") (pintype "passive"))
      (node (ref "L2") (pin "2") (pinfunction "2_2") (pintype "passive"))
      (node (ref "L6") (pin "1") (pinfunction "1_1") (pintype "passive"))
    )
    (net (code "15") (name "Net-(IC2-CAP+)") (class "Default")
      (node (ref "C72") (pin "2") (pinfunction "2_2") (pintype "passive"))
      (node (ref "IC2") (pin "2") (pinfunction "CAP+_2") (pintype "passive"))
    )
    (net (code "16") (name "Net-(IC2-CAP-)") (class "Default")
      (node (ref "C72") (pin "1") (pinfunction "1_1") (pintype "passive"))
      (node (ref "IC2") (pin "4") (pinfunction "CAP-_4") (pintype "power_in"))
    )
    (net (code "17") (name "Net-(IC21-IN-Pad1)") (class "Default")
      (node (ref "IC21") (pin "1") (pinfunction "IN_1") (pintype "input"))
      (node (ref "IC21") (pin "2") (pinfunction "IN_2") (pintype "input"))
      (node (ref "L6") (pin "2") (pinfunction "2_2") (pintype "passive"))
    )
    (net (code "18") (name "Net-(IC21-PGFB)") (class "Default")
      (node (ref "IC21") (pin "6") (pinfunction "PGFB_6") (pintype "input"))
      (node (ref "R100") (pin "2") (pinfunction "2_2") (pintype "passive"))
      (node (ref "R207") (pin "1") (pinfunction "1_1") (pintype "passive"))
    )
    (net (code "19") (name "Net-(IC21-SET)") (class "Default")
      (node (ref "C91") (pin "1") (pinfunction "1_1") (pintype "passive"))
      (node (ref "IC21") (pin "7") (pinfunction "SET_7") (pintype "input"))
      (node (ref "R11") (pin "1") (pinfunction "1_1") (pintype "passive"))
    )
    (net (code "20") (name "Net-(IC31-BST)") (class "Default")
      (node (ref "C100") (pin "1") (pinfunction "1_1") (pintype "passive"))
      (node (ref "IC31") (pin "6") (pinfunction "BST_6") (pintype "input"))
    )
    (net (code "21") (name "Net-(IC31-FB)") (class "Default")
      (node (ref "IC31") (pin "4") (pinfunction "FB_4") (pintype "input"))
      (node (ref "R135") (pin "1") (pinfunction "1_1") (pintype "passive"))
      (node (ref "R136") (pin "2") (pinfunction "2_2") (pintype "passive"))
    )
    (net (code "22") (name "Net-(IC31-SW)") (class "Default")
      (node (ref "C100") (pin "2") (pinfunction "2_2") (pintype "passive"))
      (node (ref "IC31") (pin "2") (pinfunction "SW_2") (pintype "output"))
      (node (ref "L5") (pin "1") (pinfunction "1_1") (pintype "passive"))
    )
    (net (code "23") (name "Net-(IC31-VIN)") (class "Default")
      (node (ref "C102") (pin "2") (pinfunction "2_2") (pintype "passive"))
      (node (ref "C75") (pin "1") (pinfunction "1_1") (pintype "passive"))
      (node (ref "IC31") (pin "3") (pinfunction "VIN_3") (pintype "input"))
      (node (ref "L12") (pin "2") (pinfunction "2_2") (pintype "passive"))
    )
    (net (code "24") (name "Net-(IC49-CLKOUT1)") (class "Default")
      (node (ref "IC49") (pin "E6") (pinfunction "CLKOUT1_E6") (pintype "output"))
      (node (ref "IC49") (pin "H7") (pinfunction "SYNC2_H7") (pintype "input"))
    )
    (net (code "25") (name "Net-(IC49-FBX1)") (class "Default")
      (node (ref "IC49") (pin "C1") (pinfunction "FBX1_C1") (pintype "output"))
      (node (ref "R40") (pin "1") (pinfunction "1_1") (pintype "passive"))
    )
    (net (code "26") (name "Net-(IC49-FXB2)") (class "Default")
      (node (ref "IC49") (pin "J1") (pinfunction "FXB2_J1") (pintype "output"))
      (node (ref "R21") (pin "1") (pinfunction "1_1") (pintype "passive"))
    )
    (net (code "27") (name "Net-(IC49-RT1)") (class "Default")
      (node (ref "IC49") (pin "E7") (pinfunction "RT1_E7") (pintype "input"))
      (node (ref "R213") (pin "2") (pinfunction "2_2") (pintype "passive"))
    )
    (net (code "28") (name "Net-(IC49-RT2)") (class "Default")
      (node (ref "IC49") (pin "G7") (pinfunction "RT2_G7") (pintype "input"))
      (node (ref "R212") (pin "2") (pinfunction "2_2") (pintype "passive"))
    )
    (net (code "29") (name "Net-(IC49-SS1)") (class "Default")
      (node (ref "C441") (pin "2") (pinfunction "2_2") (pintype "passive"))
      (node (ref "IC49") (pin "C7") (pinfunction "SS1_C7") (pintype "passive"))
    )
    (net (code "30") (name "Net-(IC49-SS2)") (class "Default")
      (node (ref "C442") (pin "2") (pinfunction "2_2") (pintype "passive"))
      (node (ref "IC49") (pin "J7") (pinfunction "SS2_J7") (pintype "passive"))
    )
    (net (code "31") (name "Net-(IC49-SYNC1)") (class "Default")
      (node (ref "IC49") (pin "D7") (pinfunction "SYNC1_D7") (pintype "input"))
      (node (ref "R43") (pin "2") (pinfunction "2_2") (pintype "passive"))
    )
    (net (code "32") (name "Net-(LD1-A)") (class "Default")
      (node (ref "LD1") (pin "2") (pinfunction "A_2") (pintype "passive"))
      (node (ref "R4") (pin "1") (pinfunction "1_1") (pintype "passive"))
    )
    (net (code "33") (name "Net-(LD2-A)") (class "Default")
      (node (ref "LD2") (pin "2") (pinfunction "A_2") (pintype "passive"))
      (node (ref "R5") (pin "1") (pinfunction "1_1") (pintype "passive"))
    )
    (net (code "34") (name "Net-(LD10-A)") (class "Default")
      (node (ref "LD10") (pin "2") (pinfunction "A_2") (pintype "passive"))
      (node (ref "R131") (pin "1") (pinfunction "1_1") (pintype "passive"))
    )
    (net (code "35") (name "Net-(LD11-A)") (class "Default")
      (node (ref "LD11") (pin "2") (pinfunction "A_2") (pintype "passive"))
      (node (ref "R1") (pin "1") (pinfunction "1_1") (pintype "passive"))
    )
    (net (code "36") (name "Net-(LD14-C)") (class "Default")
      (node (ref "LD14") (pin "1") (pinfunction "C_1") (pintype "passive"))
      (node (ref "R163") (pin "2") (pinfunction "2_2") (pintype "passive"))
    )
    (net (code "37") (name "Net-(LD15-A)") (class "Default")
      (node (ref "LD15") (pin "2") (pinfunction "A_2") (pintype "passive"))
      (node (ref "R225") (pin "1") (pinfunction "1_1") (pintype "passive"))
    )
    (net (code "38") (name "Net-(R11-Pad2)") (class "Default")
      (node (ref "R11") (pin "2") (pinfunction "2_2") (pintype "passive"))
      (node (ref "R142") (pin "1") (pinfunction "1_1") (pintype "passive"))
    )
    (net (code "39") (name "Net-(R21-Pad2)") (class "Default")
      (node (ref "R21") (pin "2") (pinfunction "2_2") (pintype "passive"))
      (node (ref "R26") (pin "1") (pinfunction "1_1") (pintype "passive"))
    )
    (net (code "40") (name "Net-(R207-Pad2)") (class "Default")
      (node (ref "R207") (pin "2") (pinfunction "2_2") (pintype "passive"))
      (node (ref "R226") (pin "1") (pinfunction "1_1") (pintype "passive"))
    )
    (net (code "41") (name "Net-(R224-Pad1)") (class "Default")
      (node (ref "R224") (pin "1") (pinfunction "1_1") (pintype "passive"))
      (node (ref "R40") (pin "2") (pinfunction "2_2") (pintype "passive"))
      (node (ref "R41") (pin "1") (pinfunction "1_1") (pintype "passive"))
    )
    (net (code "42") (name "Net-(R225-Pad2)") (class "Default")
      (node (ref "R225") (pin "2") (pinfunction "2_2") (pintype "passive"))
      (node (ref "R42") (pin "1") (pinfunction "1_1") (pintype "passive"))
    )
    (net (code "43") (name "P3V3") (class "Default")
      (node (ref "C103") (pin "2") (pinfunction "2_2") (pintype "passive"))
      (node (ref "C32") (pin "2") (pinfunction "2_2") (pintype "passive"))
      (node (ref "C77") (pin "2") (pinfunction "2_2") (pintype "passive"))
      (node (ref "D7") (pin "2") (pinfunction "A_2") (pintype "passive"))
      (node (ref "L5") (pin "2") (pinfunction "2_2") (pintype "passive"))
      (node (ref "R1") (pin "2") (pinfunction "2_2") (pintype "passive"))
      (node (ref "R135") (pin "2") (pinfunction "2_2") (pintype "passive"))
      (node (ref "TP2") (pin "1") (pinfunction "1_1") (pintype "bidirectional"))
    )
    (net (code "44") (name "P3V3_DIOT") (class "Default")
      (node (ref "C13") (pin "1") (pinfunction "1_1") (pintype "passive"))
      (node (ref "D1") (pin "2") (pinfunction "A_2") (pintype "passive"))
      (node (ref "IC41") (pin "5") (pinfunction "OUT_5") (pintype "power_in"))
      (node (ref "R4") (pin "2") (pinfunction "2_2") (pintype "passive"))
      (node (ref "TP9") (pin "1") (pinfunction "1_1") (pintype "bidirectional"))
    )
    (net (code "45") (name "P3V3_MP") (class "Default")
      (node (ref "D1") (pin "1") (pinfunction "C_1") (pintype "passive"))
      (node (ref "D7") (pin "1") (pinfunction "C_1") (pintype "passive"))
    )
    (net (code "46") (name "P5V4A") (class "Default")
      (node (ref "C1") (pin "2") (pinfunction "2_2") (pintype "passive"))
      (node (ref "C83") (pin "2") (pinfunction "2_2") (pintype "passive"))
      (node (ref "C90") (pin "2") (pinfunction "2_2") (pintype "passive"))
      (node (ref "IC21") (pin "10") (pinfunction "OUT_10") (pintype "output"))
      (node (ref "IC21") (pin "9") (pinfunction "OUTS_9") (pintype "output"))
      (node (ref "R226") (pin "2") (pinfunction "2_2") (pintype "passive"))
      (node (ref "R5") (pin "2") (pinfunction "2_2") (pintype "passive"))
      (node (ref "TP8") (pin "1") (pinfunction "1_1") (pintype "bidirectional"))
    )
    (net (code "47") (name "P12V0") (class "Default")
      (node (ref "C71") (pin "2") (pinfunction "2_2") (pintype "passive"))
      (node (ref "C74") (pin "2") (pinfunction "2_2") (pintype "passive"))
      (node (ref "C98") (pin "1") (pinfunction "1_1") (pintype "passive"))
      (node (ref "D11") (pin "1") (pinfunction "C_1") (pintype "passive"))
      (node (ref "FL1") (pin "2") (pinfunction "CB_2") (pintype "passive"))
      (node (ref "IC2") (pin "8") (pinfunction "V+_8") (pintype "input"))
      (node (ref "L12") (pin "1") (pinfunction "1_1") (pintype "passive"))
      (node (ref "L2") (pin "1") (pinfunction "1_1") (pintype "passive"))
      (node (ref "L4") (pin "1") (pinfunction "1_1") (pintype "passive"))
      (node (ref "R131") (pin "2") (pinfunction "2_2") (pintype "passive"))
      (node (ref "TP1") (pin "1") (pinfunction "1_1") (pintype "bidirectional"))
    )
    (net (code "48") (name "P12V0F") (class "Default")
      (node (ref "CON1") (pin "3") (pinfunction "3_3") (pintype "bidirectional"))
      (node (ref "CON1") (pin "4") (pinfunction "4_4") (pintype "bidirectional"))
      (node (ref "FL1") (pin "1") (pinfunction "B_1") (pintype "passive"))
      (node (ref "J10") (pin "3") (pinfunction "3_3") (pintype "bidirectional"))
    )
    (net (code "49") (name "P12V0_CPCIS") (class "Default")
      (node (ref "C8") (pin "2") (pinfunction "2_2") (pintype "passive"))
      (node (ref "IC41") (pin "1") (pinfunction "IN_1") (pintype "input"))
      (node (ref "IC41") (pin "3") (pinfunction "EN_3") (pintype "input"))
    )
    (net (code "50") (name "P15V0") (class "Default")
      (node (ref "C503") (pin "1") (pinfunction "1_1") (pintype "passive"))
      (node (ref "C529") (pin "2") (pinfunction "2_2") (pintype "passive"))
      (node (ref "C530") (pin "2") (pinfunction "2_2") (pintype "passive"))
      (node (ref "L9") (pin "2") (pinfunction "2_2") (pintype "passive"))
      (node (ref "R42") (pin "2") (pinfunction "2_2") (pintype "passive"))
      (node (ref "TP56") (pin "1") (pinfunction "1_1") (pintype "bidirectional"))
    )
    (net (code "51") (name "unconnected-(IC2-Boost-Pad1)") (class "Default")
      (node (ref "IC2") (pin "1") (pinfunction "Boost_1") (pintype "passive"))
    )
    (net (code "52") (name "unconnected-(IC2-LV-Pad6)") (class "Default")
      (node (ref "IC2") (pin "6") (pinfunction "LV_6") (pintype "output"))
    )
    (net (code "53") (name "unconnected-(IC2-OSC-Pad7)") (class "Default")
      (node (ref "IC2") (pin "7") (pinfunction "OSC_7") (pintype "passive"))
    )
    (net (code "54") (name "unconnected-(IC31-EN-Pad5)") (class "Default")
      (node (ref "IC31") (pin "5") (pinfunction "EN_5") (pintype "input+no_connect"))
    )
    (net (code "55") (name "unconnected-(IC41-BYP-Pad4)") (class "Default")
      (node (ref "IC41") (pin "4") (pinfunction "BYP_4") (pintype "passive+no_connect"))
    )
    (net (code "56") (name "unconnected-(IC49-CLKOUT2-PadG6)") (class "Default")
      (node (ref "IC49") (pin "G6") (pinfunction "CLKOUT2_G6") (pintype "output+no_connect"))
    )
    (net (code "57") (name "unconnected-(IC49-SHARE1-PadF3)") (class "Default")
      (node (ref "IC49") (pin "F3") (pinfunction "SHARE1_F3") (pintype "input+no_connect"))
    )
    (net (code "58") (name "unconnected-(IC49-SHARE2-PadF4)") (class "Default")
      (node (ref "IC49") (pin "F4") (pinfunction "SHARE2_F4") (pintype "input+no_connect"))
    )
    (net (code "59") (name "unconnected-(J10-Pad2)") (class "Default")
      (node (ref "J10") (pin "2") (pinfunction "2_2") (pintype "bidirectional"))
    )
  )
)
